# hub.net
KiCad netlist of a schematic drawn in EAGLE
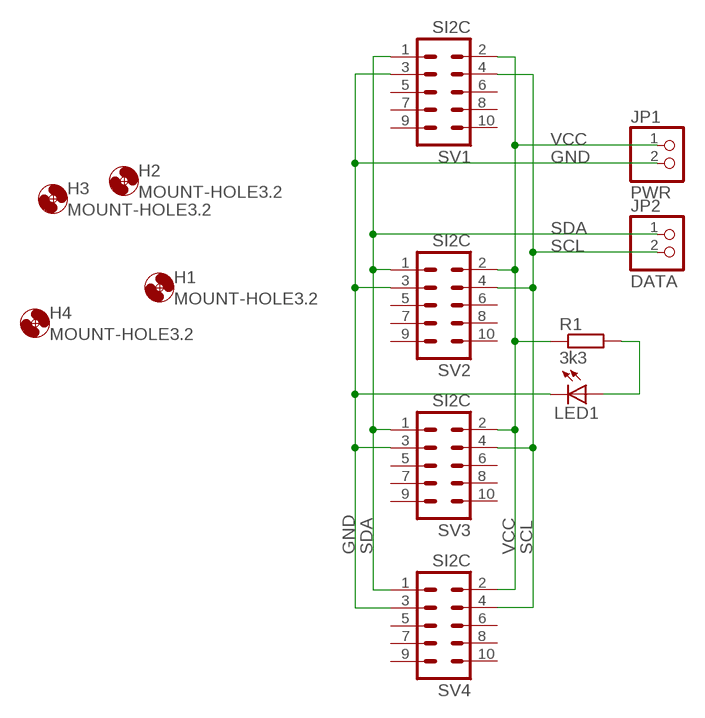
[diagram p0: schematic, sheet 1]

(export (version "E")
  (design (tool "Eeschema 10.0.6"))
  (components
    (comp (ref "H1")
      (value "MOUNT-HOLE3.2")
      (footprint "eagle-import:3,2")
      (libsource (lib "eagle-import") (part "MOUNT-HOLE3.2"))
    )
    (comp (ref "H2")
      (value "MOUNT-HOLE3.2")
      (footprint "eagle-import:3,2")
      (libsource (lib "eagle-import") (part "MOUNT-HOLE3.2"))
    )
    (comp (ref "H3")
      (value "MOUNT-HOLE3.2")
      (footprint "eagle-import:3,2")
      (libsource (lib "eagle-import") (part "MOUNT-HOLE3.2"))
    )
    (comp (ref "H4")
      (value "MOUNT-HOLE3.2")
      (footprint "eagle-import:3,2")
      (libsource (lib "eagle-import") (part "MOUNT-HOLE3.2"))
    )
    (comp (ref "JP1")
      (value "PWR")
      (footprint "eagle-import:1X02")
      (libsource (lib "eagle-import") (part "PINHD-1X2"))
    )
    (comp (ref "JP2")
      (value "DATA")
      (footprint "eagle-import:1X02")
      (libsource (lib "eagle-import") (part "PINHD-1X2"))
    )
    (comp (ref "LED1")
      (value "LED3MM")
      (footprint "eagle-import:LED3MM")
      (libsource (lib "eagle-import") (part "LED3MM"))
    )
    (comp (ref "R1")
      (value "3k3")
      (footprint "eagle-import:0204_7")
      (libsource (lib "eagle-import") (part "R-EU_0204/7"))
    )
    (comp (ref "SV1")
      (value "SI2C")
      (footprint "eagle-import:ML10")
      (libsource (lib "eagle-import") (part "ML10"))
    )
    (comp (ref "SV2")
      (value "SI2C")
      (footprint "eagle-import:ML10")
      (libsource (lib "eagle-import") (part "ML10"))
    )
    (comp (ref "SV3")
      (value "SI2C")
      (footprint "eagle-import:ML10")
      (libsource (lib "eagle-import") (part "ML10"))
    )
    (comp (ref "SV4")
      (value "SI2C")
      (footprint "eagle-import:ML10")
      (libsource (lib "eagle-import") (part "ML10"))
    )
  )
  (nets
    (net (code "1") (name "/GND") (class "Default")
      (node (ref "JP1") (pin "2") (pinfunction "2_2") (pintype "passive"))
      (node (ref "LED1") (pin "K") (pinfunction "C_K") (pintype "passive"))
      (node (ref "SV1") (pin "3") (pinfunction "3_3") (pintype "passive"))
      (node (ref "SV2") (pin "3") (pinfunction "3_3") (pintype "passive"))
      (node (ref "SV3") (pin "3") (pinfunction "3_3") (pintype "passive"))
      (node (ref "SV4") (pin "3") (pinfunction "3_3") (pintype "passive"))
    )
    (net (code "2") (name "/SCL") (class "Default")
      (node (ref "JP2") (pin "2") (pinfunction "2_2") (pintype "passive"))
      (node (ref "SV1") (pin "4") (pinfunction "4_4") (pintype "passive"))
      (node (ref "SV2") (pin "4") (pinfunction "4_4") (pintype "passive"))
      (node (ref "SV3") (pin "4") (pinfunction "4_4") (pintype "passive"))
      (node (ref "SV4") (pin "4") (pinfunction "4_4") (pintype "passive"))
    )
    (net (code "3") (name "/SDA") (class "Default")
      (node (ref "JP2") (pin "1") (pinfunction "1_1") (pintype "passive"))
      (node (ref "SV1") (pin "1") (pinfunction "1_1") (pintype "passive"))
      (node (ref "SV2") (pin "1") (pinfunction "1_1") (pintype "passive"))
      (node (ref "SV3") (pin "1") (pinfunction "1_1") (pintype "passive"))
      (node (ref "SV4") (pin "1") (pinfunction "1_1") (pintype "passive"))
    )
    (net (code "4") (name "/VCC") (class "Default")
      (node (ref "JP1") (pin "1") (pinfunction "1_1") (pintype "passive"))
      (node (ref "R1") (pin "1") (pinfunction "1_1") (pintype "passive"))
      (node (ref "SV1") (pin "2") (pinfunction "2_2") (pintype "passive"))
      (node (ref "SV2") (pin "2") (pinfunction "2_2") (pintype "passive"))
      (node (ref "SV3") (pin "2") (pinfunction "2_2") (pintype "passive"))
      (node (ref "SV4") (pin "2") (pinfunction "2_2") (pintype "passive"))
    )
    (net (code "5") (name "Net-(LED1-PadA)") (class "Default")
      (node (ref "LED1") (pin "A") (pinfunction "A_A") (pintype "passive"))
      (node (ref "R1") (pin "2") (pinfunction "2_2") (pintype "passive"))
    )
    (net (code "6") (name "unconnected-(SV1-Pad5)") (class "Default")
      (node (ref "SV1") (pin "5") (pinfunction "5_5") (pintype "passive"))
    )
    (net (code "7") (name "unconnected-(SV1-Pad6)") (class "Default")
      (node (ref "SV1") (pin "6") (pinfunction "6_6") (pintype "passive"))
    )
    (net (code "8") (name "unconnected-(SV1-Pad7)") (class "Default")
      (node (ref "SV1") (pin "7") (pinfunction "7_7") (pintype "passive"))
    )
    (net (code "9") (name "unconnected-(SV1-Pad8)") (class "Default")
      (node (ref "SV1") (pin "8") (pinfunction "8_8") (pintype "passive"))
    )
    (net (code "10") (name "unconnected-(SV1-Pad9)") (class "Default")
      (node (ref "SV1") (pin "9") (pinfunction "9_9") (pintype "passive"))
    )
    (net (code "11") (name "unconnected-(SV1-Pad10)") (class "Default")
      (node (ref "SV1") (pin "10") (pinfunction "10_10") (pintype "passive"))
    )
    (net (code "12") (name "unconnected-(SV2-Pad5)") (class "Default")
      (node (ref "SV2") (pin "5") (pinfunction "5_5") (pintype "passive"))
    )
    (net (code "13") (name "unconnected-(SV2-Pad6)") (class "Default")
      (node (ref "SV2") (pin "6") (pinfunction "6_6") (pintype "passive"))
    )
    (net (code "14") (name "unconnected-(SV2-Pad7)") (class "Default")
      (node (ref "SV2") (pin "7") (pinfunction "7_7") (pintype "passive"))
    )
    (net (code "15") (name "unconnected-(SV2-Pad8)") (class "Default")
      (node (ref "SV2") (pin "8") (pinfunction "8_8") (pintype "passive"))
    )
    (net (code "16") (name "unconnected-(SV2-Pad9)") (class "Default")
      (node (ref "SV2") (pin "9") (pinfunction "9_9") (pintype "passive"))
    )
    (net (code "17") (name "unconnected-(SV2-Pad10)") (class "Default")
      (node (ref "SV2") (pin "10") (pinfunction "10_10") (pintype "passive"))
    )
    (net (code "18") (name "unconnected-(SV3-Pad5)") (class "Default")
      (node (ref "SV3") (pin "5") (pinfunction "5_5") (pintype "passive"))
    )
    (net (code "19") (name "unconnected-(SV3-Pad6)") (class "Default")
      (node (ref "SV3") (pin "6") (pinfunction "6_6") (pintype "passive"))
    )
    (net (code "20") (name "unconnected-(SV3-Pad7)") (class "Default")
      (node (ref "SV3") (pin "7") (pinfunction "7_7") (pintype "passive"))
    )
    (net (code "21") (name "unconnected-(SV3-Pad8)") (class "Default")
      (node (ref "SV3") (pin "8") (pinfunction "8_8") (pintype "passive"))
    )
    (net (code "22") (name "unconnected-(SV3-Pad9)") (class "Default")
      (node (ref "SV3") (pin "9") (pinfunction "9_9") (pintype "passive"))
    )
    (net (code "23") (name "unconnected-(SV3-Pad10)") (class "Default")
      (node (ref "SV3") (pin "10") (pinfunction "10_10") (pintype "passive"))
    )
    (net (code "24") (name "unconnected-(SV4-Pad5)") (class "Default")
      (node (ref "SV4") (pin "5") (pinfunction "5_5") (pintype "passive"))
    )
    (net (code "25") (name "unconnected-(SV4-Pad6)") (class "Default")
      (node (ref "SV4") (pin "6") (pinfunction "6_6") (pintype "passive"))
    )
    (net (code "26") (name "unconnected-(SV4-Pad7)") (class "Default")
      (node (ref "SV4") (pin "7") (pinfunction "7_7") (pintype "passive"))
    )
    (net (code "27") (name "unconnected-(SV4-Pad8)") (class "Default")
      (node (ref "SV4") (pin "8") (pinfunction "8_8") (pintype "passive"))
    )
    (net (code "28") (name "unconnected-(SV4-Pad9)") (class "Default")
      (node (ref "SV4") (pin "9") (pinfunction "9_9") (pintype "passive"))
    )
    (net (code "29") (name "unconnected-(SV4-Pad10)") (class "Default")
      (node (ref "SV4") (pin "10") (pinfunction "10_10") (pintype "passive"))
    )
  )
)
